# 06_KEY.net
KiCad netlist of a schematic drawn in Altium Designer
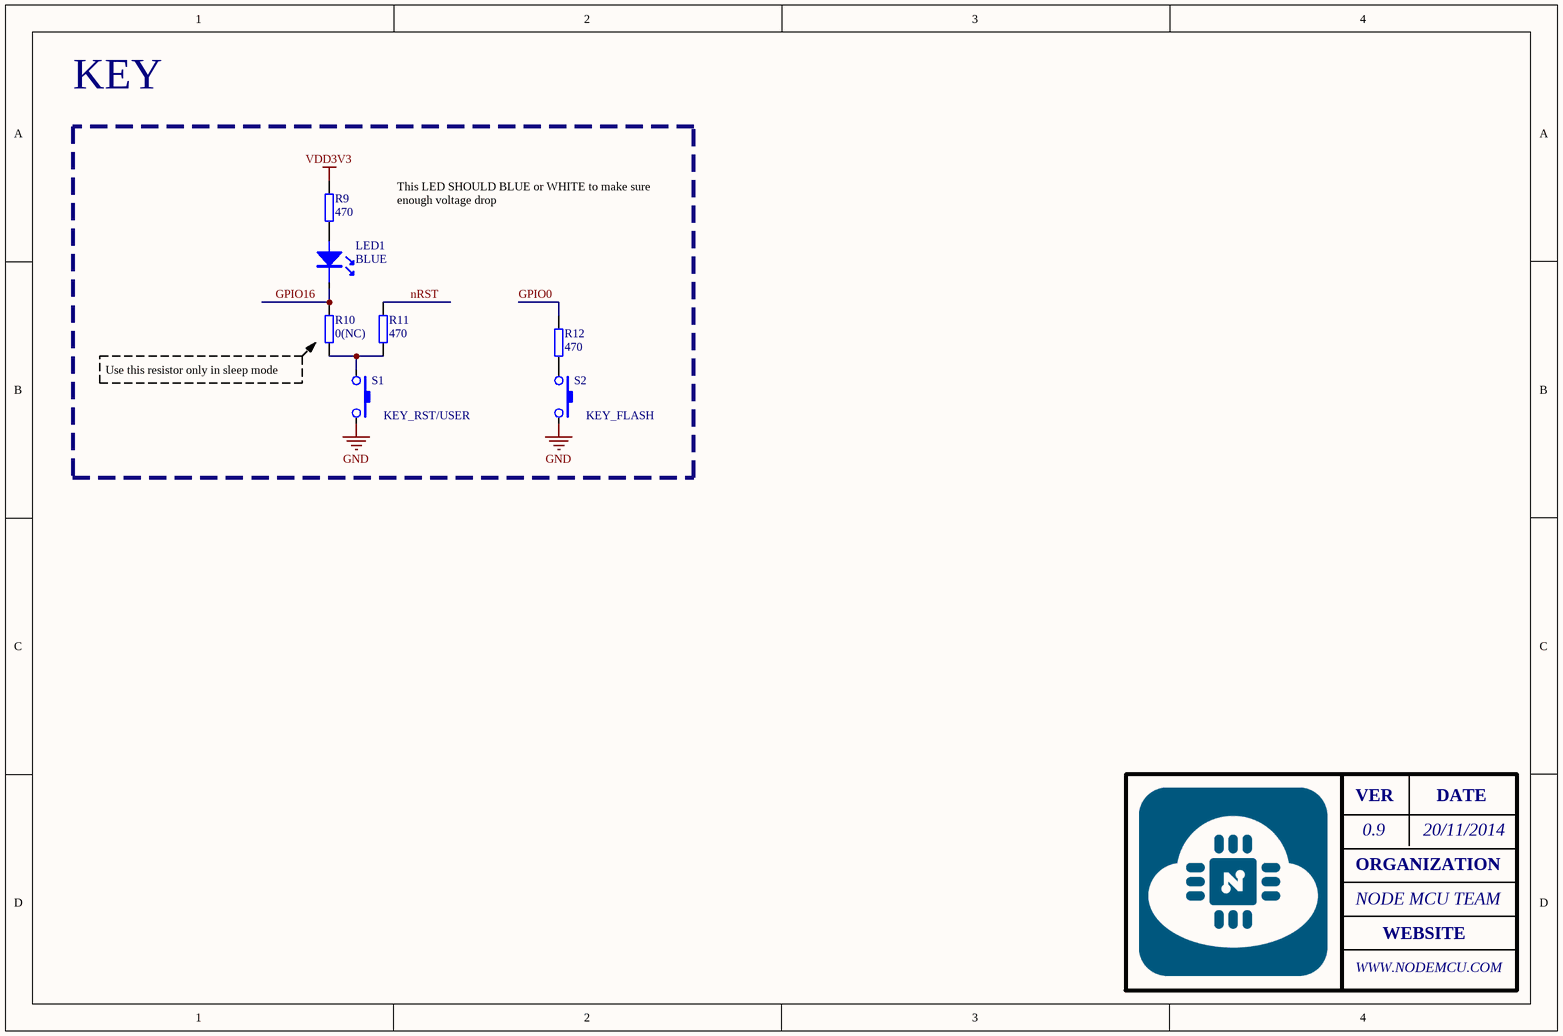
[diagram p0: 06_KEY.SchDoc]

(export (version "E")
  (design (tool "Eeschema 10.0.6"))
  (components
    (comp (ref "LED1")
      (value "BLUE")
      (footprint "SMT_LED_0603")
      (description "SMT LED")
      (libsource (lib "Vowstar_Basic_Device") (part "SMT_LED_0603"))
    )
    (comp (ref "R9")
      (value "470")
      (footprint "SMT_R_0603")
      (description "Surface mount resistor 0402")
      (libsource (lib "Vowstar_Basic_Device") (part "SMT_R_0402"))
    )
    (comp (ref "R10")
      (value "0(NC)")
      (footprint "SMT_R_0603")
      (description "Surface mount resistor 0402")
      (libsource (lib "Vowstar_Basic_Device") (part "SMT_R_0402"))
    )
    (comp (ref "R11")
      (value "470")
      (footprint "SMT_R_0603")
      (description "Surface mount resistor 0402")
      (libsource (lib "Vowstar_Basic_Device") (part "SMT_R_0402"))
    )
    (comp (ref "R12")
      (value "470")
      (footprint "SMT_R_0603")
      (description "Surface mount resistor 0402")
      (libsource (lib "Vowstar_Basic_Device") (part "SMT_R_0402"))
    )
    (comp (ref "S1")
      (value "KEY_RST/USER")
      (footprint "SMT_SW_PTS_820")
      (description "SMT Tactile ‎Switch PTS 820 Series")
      (libsource (lib "Vowstar_Switch") (part "SMT_SW_PTS_820"))
    )
    (comp (ref "S2")
      (value "KEY_FLASH")
      (footprint "SMT_SW_PTS_820")
      (description "SMT Tactile ‎Switch PTS 820 Series")
      (libsource (lib "Vowstar_Switch") (part "SMT_SW_PTS_820"))
    )
  )
  (nets
    (net (code "1") (name "/GPIO0") (class "Default")
      (node (ref "R12") (pin "2") (pinfunction "2_2") (pintype "passive"))
    )
    (net (code "2") (name "/GPIO16") (class "Default")
      (node (ref "LED1") (pin "2") (pinfunction "K_2") (pintype "passive"))
      (node (ref "R10") (pin "2") (pinfunction "2_2") (pintype "passive"))
    )
    (net (code "3") (name "/nRST") (class "Default")
      (node (ref "R11") (pin "2") (pinfunction "2_2") (pintype "passive"))
    )
    (net (code "4") (name "GND") (class "Default")
      (node (ref "S1") (pin "2") (pinfunction "2_2") (pintype "passive"))
      (node (ref "S2") (pin "2") (pinfunction "2_2") (pintype "passive"))
    )
    (net (code "5") (name "Net-(LED1-A)") (class "Default")
      (node (ref "LED1") (pin "1") (pinfunction "A_1") (pintype "passive"))
      (node (ref "R9") (pin "1") (pinfunction "1_1") (pintype "passive"))
    )
    (net (code "6") (name "Net-(R10-Pad1)") (class "Default")
      (node (ref "R10") (pin "1") (pinfunction "1_1") (pintype "passive"))
      (node (ref "R11") (pin "1") (pinfunction "1_1") (pintype "passive"))
      (node (ref "S1") (pin "1") (pinfunction "1_1") (pintype "passive"))
    )
    (net (code "7") (name "Net-(R12-Pad1)") (class "Default")
      (node (ref "R12") (pin "1") (pinfunction "1_1") (pintype "passive"))
      (node (ref "S2") (pin "1") (pinfunction "1_1") (pintype "passive"))
    )
    (net (code "8") (name "VDD3V3") (class "Default")
      (node (ref "R9") (pin "2") (pinfunction "2_2") (pintype "passive"))
    )
  )
)
